# mainboard_rev_a.net
KiCad netlist of a schematic drawn in EAGLE
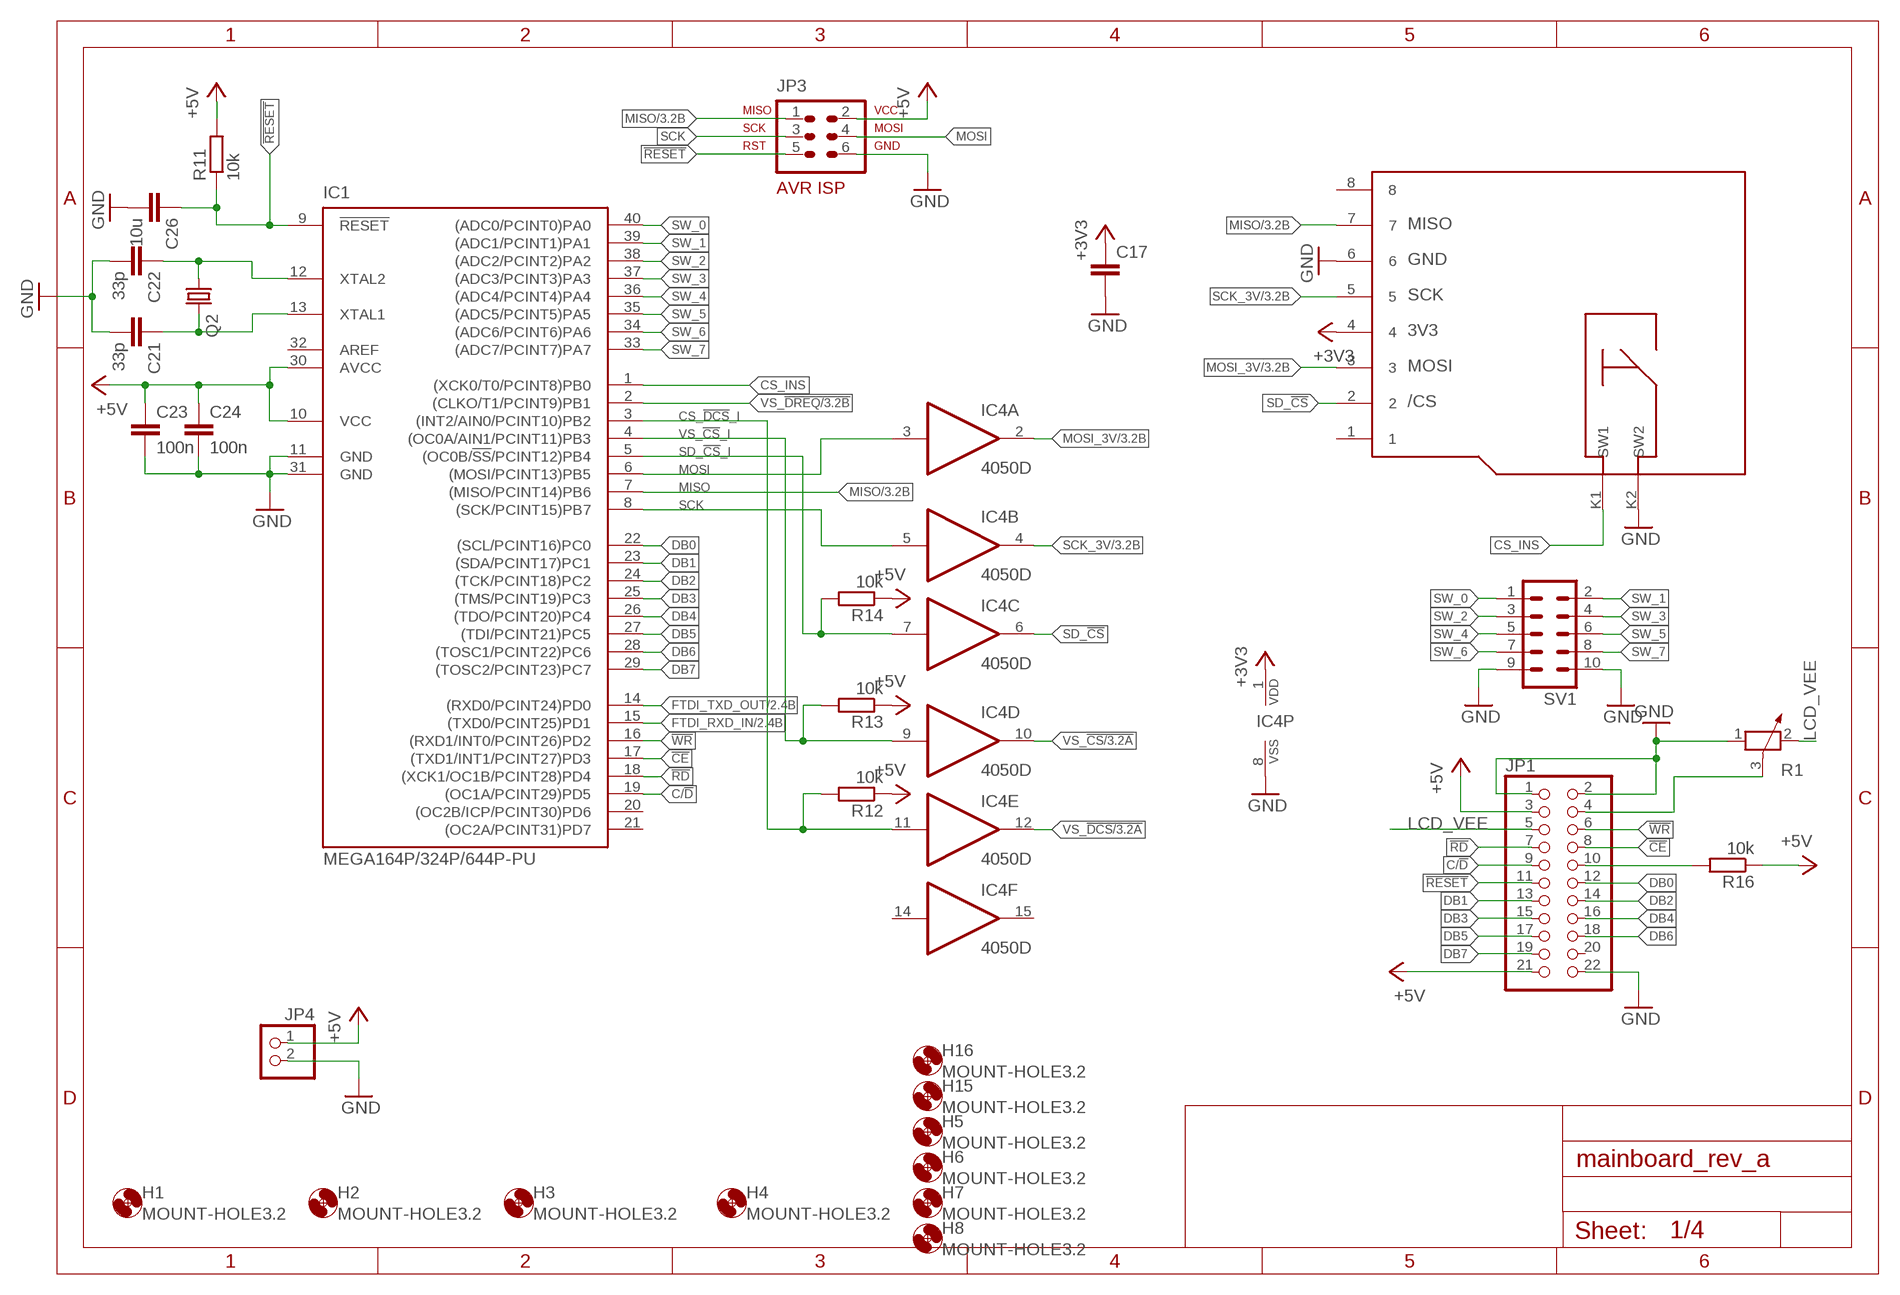
[diagram p0: schematic, sheet 1]
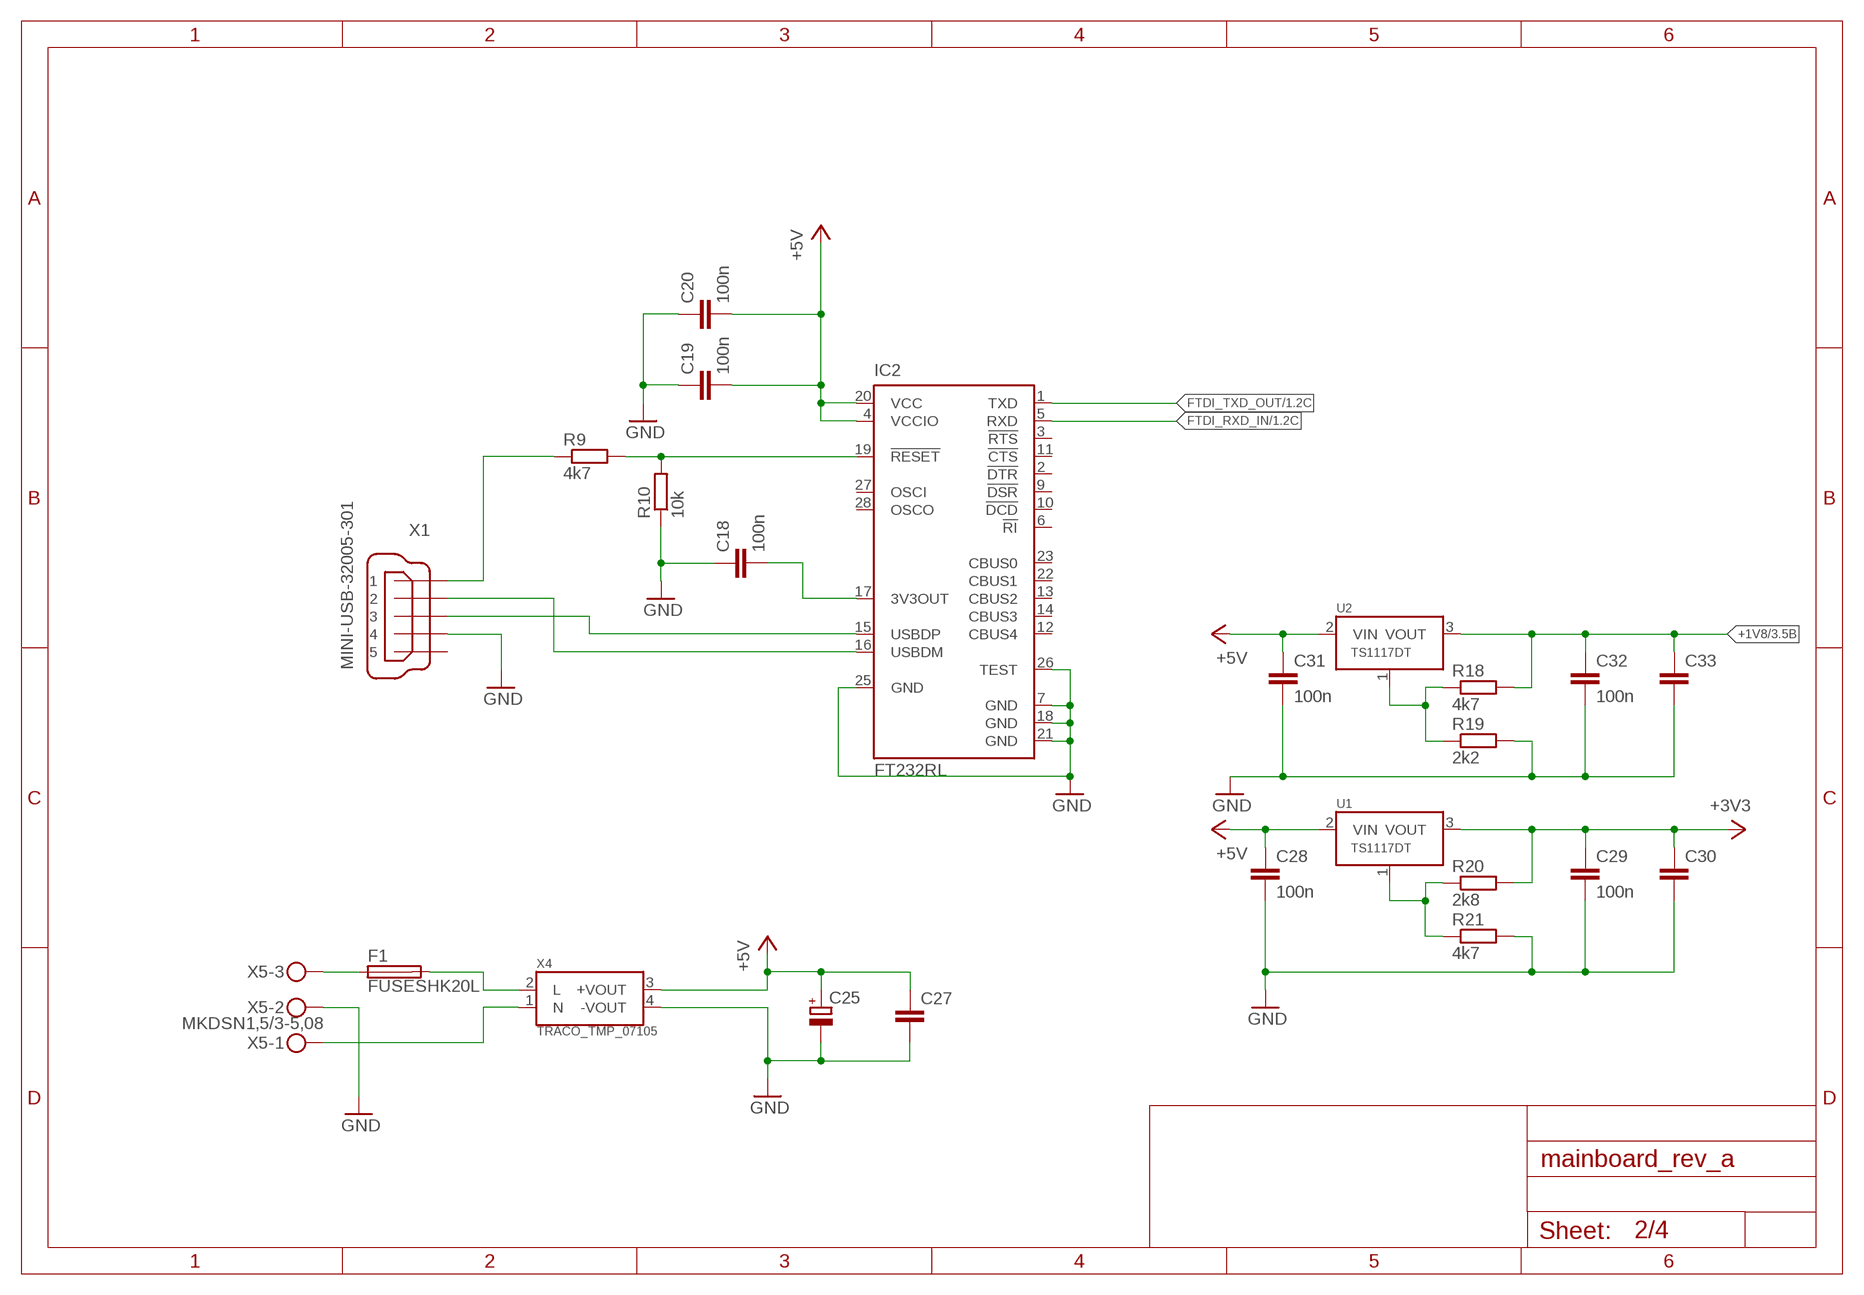
[diagram p1: schematic, sheet 2]
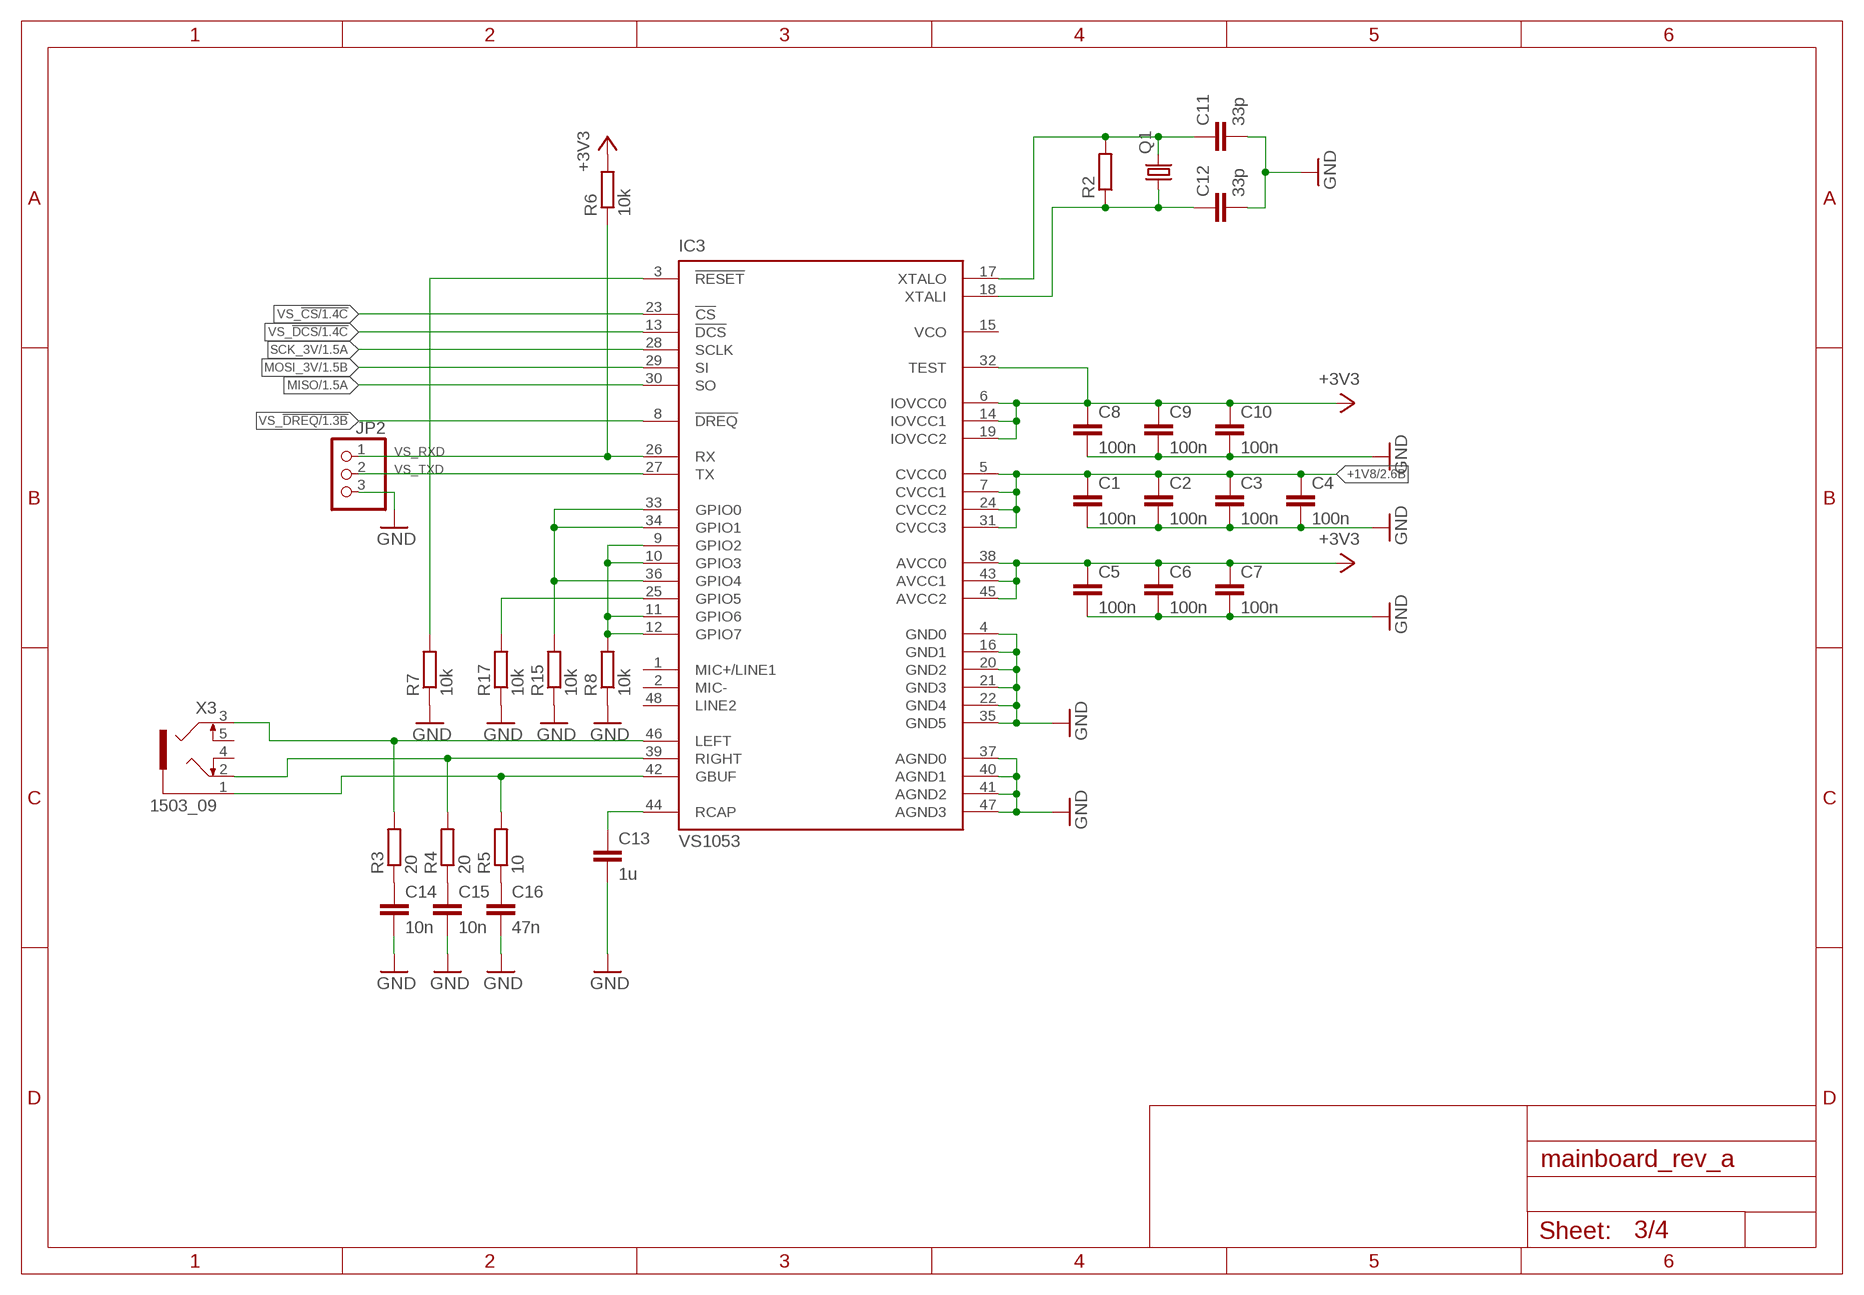
[diagram p2: schematic, sheet 3]
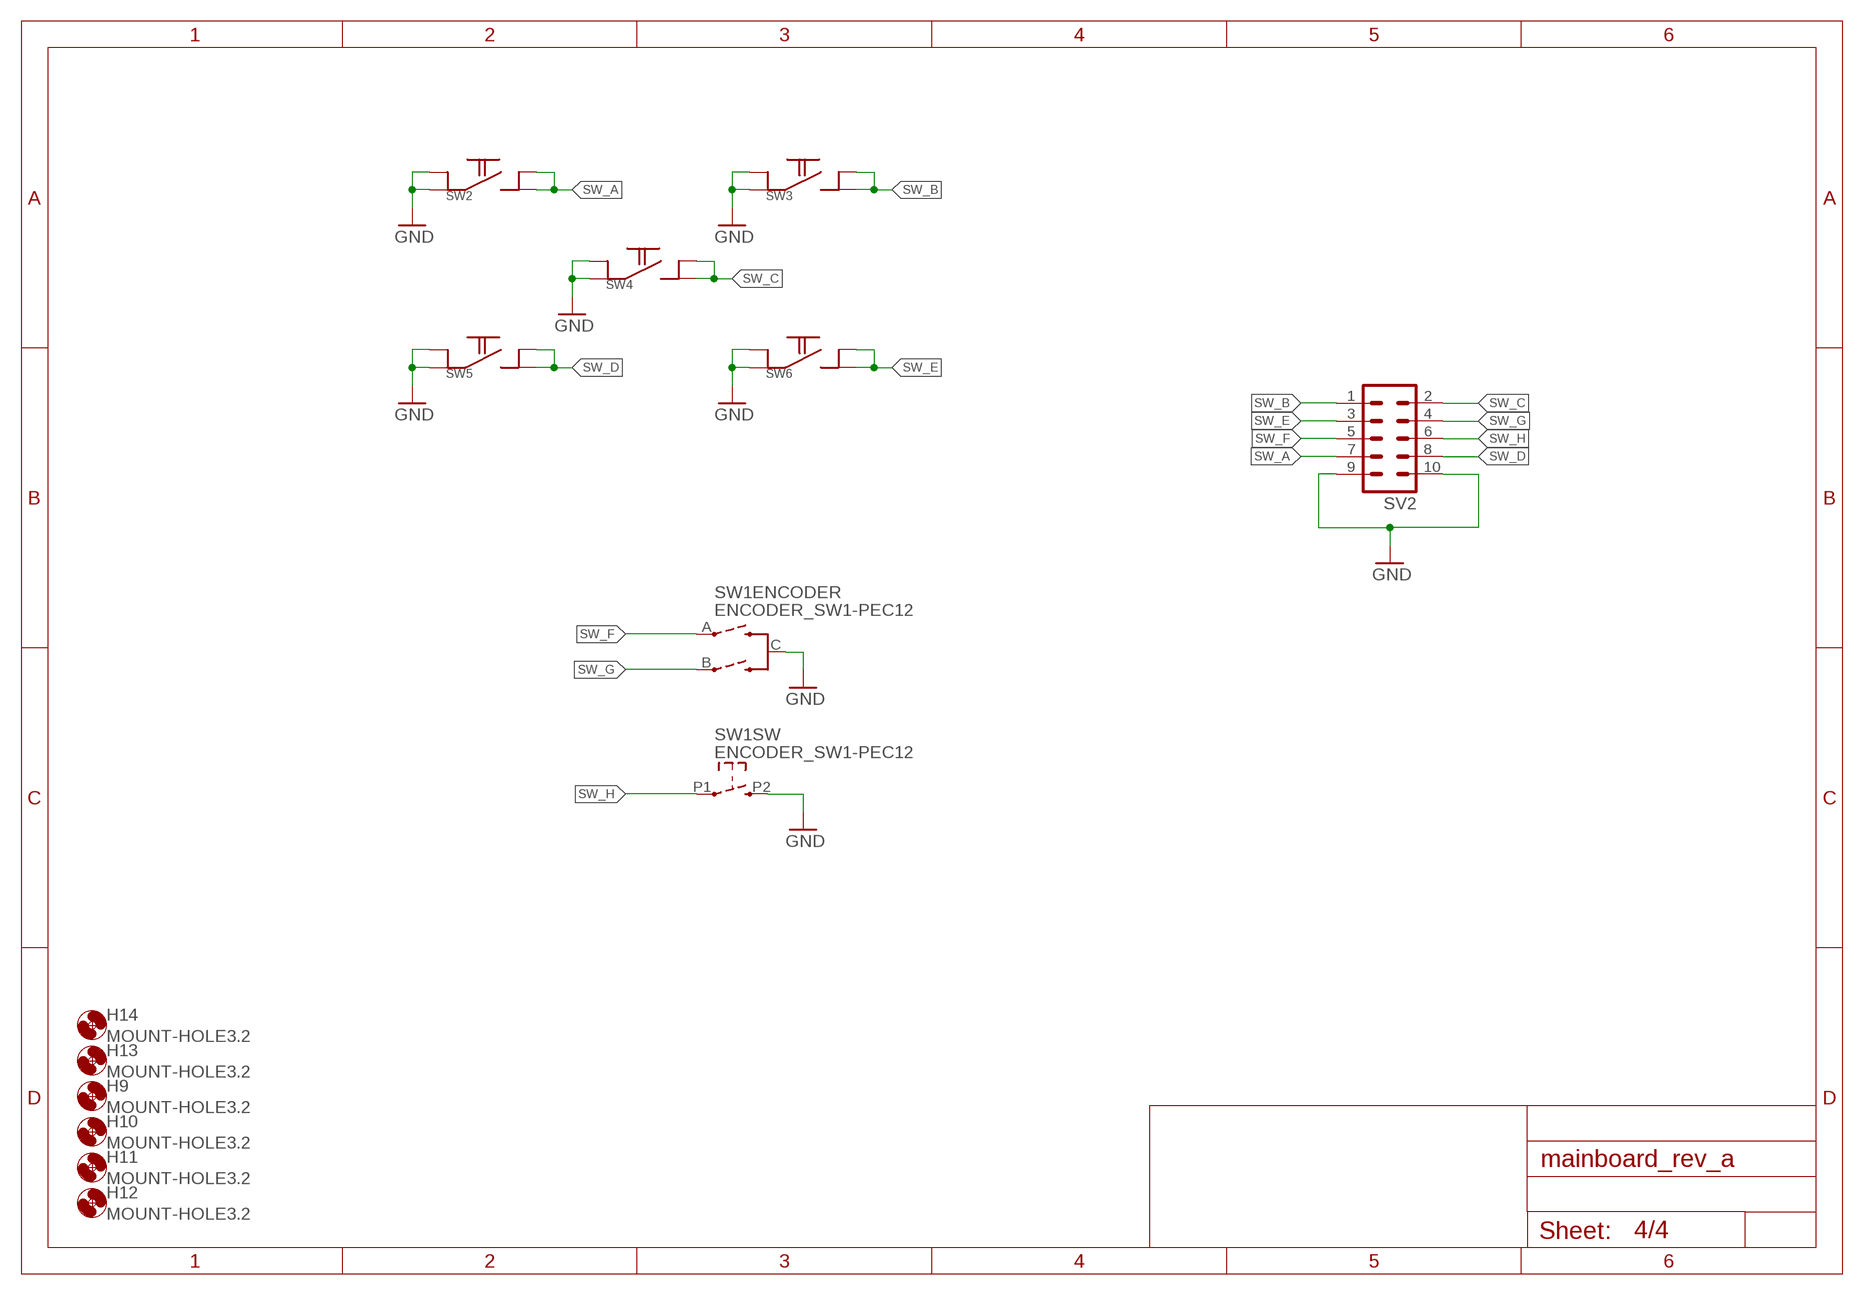
[diagram p3: schematic, sheet 4]

(export (version "E")
  (design (tool "Eeschema 10.0.6"))
  (components
    (comp (ref "H9")
      (value "MOUNT-HOLE3.2")
      (footprint "eagle-import:3,2")
      (libsource (lib "eagle-import") (part "MOUNT-HOLE3.2"))
    )
    (comp (ref "H10")
      (value "MOUNT-HOLE3.2")
      (footprint "eagle-import:3,2")
      (libsource (lib "eagle-import") (part "MOUNT-HOLE3.2"))
    )
    (comp (ref "H11")
      (value "MOUNT-HOLE3.2")
      (footprint "eagle-import:3,2")
      (libsource (lib "eagle-import") (part "MOUNT-HOLE3.2"))
    )
    (comp (ref "H12")
      (value "MOUNT-HOLE3.2")
      (footprint "eagle-import:3,2")
      (libsource (lib "eagle-import") (part "MOUNT-HOLE3.2"))
    )
    (comp (ref "H13")
      (value "MOUNT-HOLE3.2")
      (footprint "eagle-import:3,2")
      (libsource (lib "eagle-import") (part "MOUNT-HOLE3.2"))
    )
    (comp (ref "H14")
      (value "MOUNT-HOLE3.2")
      (footprint "eagle-import:3,2")
      (libsource (lib "eagle-import") (part "MOUNT-HOLE3.2"))
    )
    (comp (ref "SV2")
      (value "ML10")
      (footprint "eagle-import:ML10")
      (libsource (lib "eagle-import") (part "ML10"))
    )
    (comp (ref "SW1")
      (value "ENCODER_SW1-PEC12")
      (footprint "eagle-import:PEC12_INCREMENTAL_ENCODER")
      (libsource (lib "eagle-import") (part "ENCODER_SW1-PEC12"))
    )
    (comp (ref "SW2")
      (value "PUSHBUTTON_12X12")
      (footprint "eagle-import:PUSHBUTTON_12X12")
      (libsource (lib "eagle-import") (part "PUSHBUTTON_12X12"))
    )
    (comp (ref "SW3")
      (value "PUSHBUTTON_12X12")
      (footprint "eagle-import:PUSHBUTTON_12X12")
      (libsource (lib "eagle-import") (part "PUSHBUTTON_12X12"))
    )
    (comp (ref "SW4")
      (value "PUSHBUTTON_12X12")
      (footprint "eagle-import:PUSHBUTTON_12X12")
      (libsource (lib "eagle-import") (part "PUSHBUTTON_12X12"))
    )
    (comp (ref "SW5")
      (value "PUSHBUTTON_12X12")
      (footprint "eagle-import:PUSHBUTTON_12X12")
      (libsource (lib "eagle-import") (part "PUSHBUTTON_12X12"))
    )
    (comp (ref "SW6")
      (value "PUSHBUTTON_12X12")
      (footprint "eagle-import:PUSHBUTTON_12X12")
      (libsource (lib "eagle-import") (part "PUSHBUTTON_12X12"))
    )
    (comp (ref "C18")
      (value "100n")
      (footprint "eagle-import:C0603")
      (libsource (lib "eagle-import") (part "C-EUC0603"))
    )
    (comp (ref "C19")
      (value "100n")
      (footprint "eagle-import:C0603")
      (libsource (lib "eagle-import") (part "C-EUC0603"))
    )
    (comp (ref "C20")
      (value "100n")
      (footprint "eagle-import:C0603")
      (libsource (lib "eagle-import") (part "C-EUC0603"))
    )
    (comp (ref "C25")
      (value "CPOL-EU153CLV-0807")
      (footprint "eagle-import:153CLV-0807")
      (libsource (lib "eagle-import") (part "CPOL-EU153CLV-0807"))
    )
    (comp (ref "C27")
      (value "C-EUC1206")
      (footprint "eagle-import:C1206")
      (libsource (lib "eagle-import") (part "C-EUC1206"))
    )
    (comp (ref "C28")
      (value "100n")
      (footprint "eagle-import:C0603")
      (libsource (lib "eagle-import") (part "C-EUC0603"))
    )
    (comp (ref "C29")
      (value "100n")
      (footprint "eagle-import:C0603")
      (libsource (lib "eagle-import") (part "C-EUC0603"))
    )
    (comp (ref "C30")
      (value "C-EUC1206")
      (footprint "eagle-import:C1206")
      (libsource (lib "eagle-import") (part "C-EUC1206"))
    )
    (comp (ref "C31")
      (value "100n")
      (footprint "eagle-import:C0603")
      (libsource (lib "eagle-import") (part "C-EUC0603"))
    )
    (comp (ref "C32")
      (value "100n")
      (footprint "eagle-import:C0603")
      (libsource (lib "eagle-import") (part "C-EUC0603"))
    )
    (comp (ref "C33")
      (value "C-EUC1206")
      (footprint "eagle-import:C1206")
      (libsource (lib "eagle-import") (part "C-EUC1206"))
    )
    (comp (ref "F1")
      (value "FUSESHK20L")
      (footprint "eagle-import:SHK20L")
      (libsource (lib "eagle-import") (part "FUSESHK20L"))
    )
    (comp (ref "IC2")
      (value "FT232RL")
      (footprint "eagle-import:SSOP28")
      (libsource (lib "eagle-import") (part "FT232RL"))
    )
    (comp (ref "R9")
      (value "4k7")
      (footprint "eagle-import:R0603")
      (libsource (lib "eagle-import") (part "R-EU_R0603"))
    )
    (comp (ref "R10")
      (value "10k")
      (footprint "eagle-import:R0603")
      (libsource (lib "eagle-import") (part "R-EU_R0603"))
    )
    (comp (ref "R18")
      (value "4k7")
      (footprint "eagle-import:R0603")
      (libsource (lib "eagle-import") (part "R-EU_R0603"))
    )
    (comp (ref "R19")
      (value "2k2")
      (footprint "eagle-import:R0603")
      (libsource (lib "eagle-import") (part "R-EU_R0603"))
    )
    (comp (ref "R20")
      (value "2k8")
      (footprint "eagle-import:R0603")
      (libsource (lib "eagle-import") (part "R-EU_R0603"))
    )
    (comp (ref "R21")
      (value "4k7")
      (footprint "eagle-import:R0603")
      (libsource (lib "eagle-import") (part "R-EU_R0603"))
    )
    (comp (ref "U1")
      (value "TS1117DT")
      (footprint "eagle-import:TO252")
      (libsource (lib "eagle-import") (part "TS1117DT"))
    )
    (comp (ref "U2")
      (value "TS1117DT")
      (footprint "eagle-import:TO252")
      (libsource (lib "eagle-import") (part "TS1117DT"))
    )
    (comp (ref "X1")
      (value "MINI-USB-32005-301")
      (footprint "eagle-import:32005-301")
      (libsource (lib "eagle-import") (part "MINI-USB-32005-301"))
    )
    (comp (ref "X4")
      (value "TRACO_TMP_07105")
      (footprint "eagle-import:TRACO_TMP_07")
      (fields (field (name "MF") "TracoPower") (field (name "MPN") "TMP 07105"))
      (libsource (lib "eagle-import") (part "TRACO_TMP_07105"))
    )
    (comp (ref "X5")
      (value "MKDSN1,5/3-5,08")
      (footprint "eagle-import:MKDSN1,5_3-5,08")
      (fields (field (name "MPN") "SMKDSN1,5/3-5,08"))
      (libsource (lib "eagle-import") (part "MKDSN1,5/3-5,08"))
    )
    (comp (ref "C17")
      (value "C-EUC1206")
      (footprint "eagle-import:C1206")
      (libsource (lib "eagle-import") (part "C-EUC1206"))
    )
    (comp (ref "C21")
      (value "33p")
      (footprint "eagle-import:C0603")
      (libsource (lib "eagle-import") (part "C-EUC0603"))
    )
    (comp (ref "C22")
      (value "33p")
      (footprint "eagle-import:C0603")
      (libsource (lib "eagle-import") (part "C-EUC0603"))
    )
    (comp (ref "C23")
      (value "100n")
      (footprint "eagle-import:C0603")
      (libsource (lib "eagle-import") (part "C-EUC0603"))
    )
    (comp (ref "C24")
      (value "100n")
      (footprint "eagle-import:C0603")
      (libsource (lib "eagle-import") (part "C-EUC0603"))
    )
    (comp (ref "C26")
      (value "10u")
      (footprint "eagle-import:C1206")
      (libsource (lib "eagle-import") (part "C-EUC1206"))
    )
    (comp (ref "H1")
      (value "MOUNT-HOLE3.2")
      (footprint "eagle-import:3,2")
      (libsource (lib "eagle-import") (part "MOUNT-HOLE3.2"))
    )
    (comp (ref "H2")
      (value "MOUNT-HOLE3.2")
      (footprint "eagle-import:3,2")
      (libsource (lib "eagle-import") (part "MOUNT-HOLE3.2"))
    )
    (comp (ref "H3")
      (value "MOUNT-HOLE3.2")
      (footprint "eagle-import:3,2")
      (libsource (lib "eagle-import") (part "MOUNT-HOLE3.2"))
    )
    (comp (ref "H4")
      (value "MOUNT-HOLE3.2")
      (footprint "eagle-import:3,2")
      (libsource (lib "eagle-import") (part "MOUNT-HOLE3.2"))
    )
    (comp (ref "H5")
      (value "MOUNT-HOLE3.2")
      (footprint "eagle-import:3,2")
      (libsource (lib "eagle-import") (part "MOUNT-HOLE3.2"))
    )
    (comp (ref "H6")
      (value "MOUNT-HOLE3.2")
      (footprint "eagle-import:3,2")
      (libsource (lib "eagle-import") (part "MOUNT-HOLE3.2"))
    )
    (comp (ref "H7")
      (value "MOUNT-HOLE3.2")
      (footprint "eagle-import:3,2")
      (libsource (lib "eagle-import") (part "MOUNT-HOLE3.2"))
    )
    (comp (ref "H8")
      (value "MOUNT-HOLE3.2")
      (footprint "eagle-import:3,2")
      (libsource (lib "eagle-import") (part "MOUNT-HOLE3.2"))
    )
    (comp (ref "H15")
      (value "MOUNT-HOLE3.2")
      (footprint "eagle-import:3,2")
      (libsource (lib "eagle-import") (part "MOUNT-HOLE3.2"))
    )
    (comp (ref "H16")
      (value "MOUNT-HOLE3.2")
      (footprint "eagle-import:3,2")
      (libsource (lib "eagle-import") (part "MOUNT-HOLE3.2"))
    )
    (comp (ref "IC1")
      (value "MEGA164P/324P/644P-PU")
      (footprint "eagle-import:DIL40")
      (libsource (lib "eagle-import") (part "MEGA164P/324P/644P-PU"))
    )
    (comp (ref "IC4")
      (value "4050D")
      (footprint "eagle-import:SO16")
      (libsource (lib "eagle-import") (part "4050D"))
    )
    (comp (ref "JP1")
      (value "PINHD-2X11")
      (footprint "eagle-import:2X11")
      (libsource (lib "eagle-import") (part "PINHD-2X11"))
    )
    (comp (ref "JP3")
      (value "AVR-ISP-6VERT")
      (footprint "eagle-import:AVR-ISP-6")
      (libsource (lib "eagle-import") (part "AVR-ISP-6VERT"))
    )
    (comp (ref "JP4")
      (value "PINHD-1X2")
      (footprint "eagle-import:1X02")
      (libsource (lib "eagle-import") (part "PINHD-1X2"))
    )
    (comp (ref "Q2")
      (value "CRYSTALHC49UP")
      (footprint "eagle-import:HC49UP")
      (libsource (lib "eagle-import") (part "CRYSTALHC49UP"))
    )
    (comp (ref "R1")
      (value "POTENTIOMETER_PT_SPIN")
      (footprint "eagle-import:PT-SPIN")
      (libsource (lib "eagle-import") (part "POTENTIOMETER_PT_SPIN"))
    )
    (comp (ref "R11")
      (value "10k")
      (footprint "eagle-import:R0603")
      (libsource (lib "eagle-import") (part "R-EU_R0603"))
    )
    (comp (ref "R12")
      (value "10k")
      (footprint "eagle-import:R0603")
      (libsource (lib "eagle-import") (part "R-EU_R0603"))
    )
    (comp (ref "R13")
      (value "10k")
      (footprint "eagle-import:R0603")
      (libsource (lib "eagle-import") (part "R-EU_R0603"))
    )
    (comp (ref "R14")
      (value "10k")
      (footprint "eagle-import:R0603")
      (libsource (lib "eagle-import") (part "R-EU_R0603"))
    )
    (comp (ref "R16")
      (value "10k")
      (footprint "eagle-import:R0603")
      (libsource (lib "eagle-import") (part "R-EU_R0603"))
    )
    (comp (ref "SV1")
      (value "ML10")
      (footprint "eagle-import:ML10")
      (libsource (lib "eagle-import") (part "ML10"))
    )
    (comp (ref "X2")
      (value "MICRO-SD")
      (footprint "eagle-import:MICRO-SD")
      (libsource (lib "eagle-import") (part "MICRO-SD"))
    )
    (comp (ref "C1")
      (value "100n")
      (footprint "eagle-import:C0603")
      (libsource (lib "eagle-import") (part "C-EUC0603"))
    )
    (comp (ref "C2")
      (value "100n")
      (footprint "eagle-import:C0603")
      (libsource (lib "eagle-import") (part "C-EUC0603"))
    )
    (comp (ref "C3")
      (value "100n")
      (footprint "eagle-import:C0603")
      (libsource (lib "eagle-import") (part "C-EUC0603"))
    )
    (comp (ref "C4")
      (value "100n")
      (footprint "eagle-import:C0603")
      (libsource (lib "eagle-import") (part "C-EUC0603"))
    )
    (comp (ref "C5")
      (value "100n")
      (footprint "eagle-import:C0603")
      (libsource (lib "eagle-import") (part "C-EUC0603"))
    )
    (comp (ref "C6")
      (value "100n")
      (footprint "eagle-import:C0603")
      (libsource (lib "eagle-import") (part "C-EUC0603"))
    )
    (comp (ref "C7")
      (value "100n")
      (footprint "eagle-import:C0603")
      (libsource (lib "eagle-import") (part "C-EUC0603"))
    )
    (comp (ref "C8")
      (value "100n")
      (footprint "eagle-import:C0603")
      (libsource (lib "eagle-import") (part "C-EUC0603"))
    )
    (comp (ref "C9")
      (value "100n")
      (footprint "eagle-import:C0603")
      (libsource (lib "eagle-import") (part "C-EUC0603"))
    )
    (comp (ref "C10")
      (value "100n")
      (footprint "eagle-import:C0603")
      (libsource (lib "eagle-import") (part "C-EUC0603"))
    )
    (comp (ref "C11")
      (value "33p")
      (footprint "eagle-import:C0603")
      (libsource (lib "eagle-import") (part "C-EUC0603"))
    )
    (comp (ref "C12")
      (value "33p")
      (footprint "eagle-import:C0603")
      (libsource (lib "eagle-import") (part "C-EUC0603"))
    )
    (comp (ref "C13")
      (value "1u")
      (footprint "eagle-import:C0805")
      (libsource (lib "eagle-import") (part "C-EUC0805"))
    )
    (comp (ref "C14")
      (value "10n")
      (footprint "eagle-import:C0603")
      (libsource (lib "eagle-import") (part "C-EUC0603"))
    )
    (comp (ref "C15")
      (value "10n")
      (footprint "eagle-import:C0603")
      (libsource (lib "eagle-import") (part "C-EUC0603"))
    )
    (comp (ref "C16")
      (value "47n")
      (footprint "eagle-import:C0603")
      (libsource (lib "eagle-import") (part "C-EUC0603"))
    )
    (comp (ref "IC3")
      (value "VS1053")
      (footprint "eagle-import:LQFP-48")
      (libsource (lib "eagle-import") (part "VS1053"))
    )
    (comp (ref "JP2")
      (value "PINHD-1X3")
      (footprint "eagle-import:1X03")
      (libsource (lib "eagle-import") (part "PINHD-1X3"))
    )
    (comp (ref "Q1")
      (value "CRYSTALHC49UP")
      (footprint "eagle-import:HC49UP")
      (libsource (lib "eagle-import") (part "CRYSTALHC49UP"))
    )
    (comp (ref "R2")
      (value "R-EU_R0603")
      (footprint "eagle-import:R0603")
      (libsource (lib "eagle-import") (part "R-EU_R0603"))
    )
    (comp (ref "R3")
      (value "20")
      (footprint "eagle-import:R0603")
      (libsource (lib "eagle-import") (part "R-EU_R0603"))
    )
    (comp (ref "R4")
      (value "20")
      (footprint "eagle-import:R0603")
      (libsource (lib "eagle-import") (part "R-EU_R0603"))
    )
    (comp (ref "R5")
      (value "10")
      (footprint "eagle-import:R0603")
      (libsource (lib "eagle-import") (part "R-EU_R0603"))
    )
    (comp (ref "R6")
      (value "10k")
      (footprint "eagle-import:R0603")
      (libsource (lib "eagle-import") (part "R-EU_R0603"))
    )
    (comp (ref "R7")
      (value "10k")
      (footprint "eagle-import:R0603")
      (libsource (lib "eagle-import") (part "R-EU_R0603"))
    )
    (comp (ref "R8")
      (value "10k")
      (footprint "eagle-import:R0603")
      (libsource (lib "eagle-import") (part "R-EU_R0603"))
    )
    (comp (ref "R15")
      (value "10k")
      (footprint "eagle-import:R0603")
      (libsource (lib "eagle-import") (part "R-EU_R0603"))
    )
    (comp (ref "R17")
      (value "10k")
      (footprint "eagle-import:R0603")
      (libsource (lib "eagle-import") (part "R-EU_R0603"))
    )
    (comp (ref "X3")
      (value "1503_09")
      (footprint "eagle-import:1503_09")
      (libsource (lib "eagle-import") (part "1503_09"))
    )
  )
  (nets
    (net (code "1") (name "+1V8") (class "Default")
      (node (ref "C1") (pin "1") (pinfunction "1_1") (pintype "passive"))
      (node (ref "C2") (pin "1") (pinfunction "1_1") (pintype "passive"))
      (node (ref "C3") (pin "1") (pinfunction "1_1") (pintype "passive"))
      (node (ref "C32") (pin "1") (pinfunction "1_1") (pintype "passive"))
      (node (ref "C33") (pin "1") (pinfunction "1_1") (pintype "passive"))
      (node (ref "C4") (pin "1") (pinfunction "1_1") (pintype "passive"))
      (node (ref "IC3") (pin "24") (pinfunction "CVCC2_24") (pintype "power_in"))
      (node (ref "IC3") (pin "31") (pinfunction "CVCC3_31") (pintype "power_in"))
      (node (ref "IC3") (pin "5") (pinfunction "CVCC0_5") (pintype "power_in"))
      (node (ref "IC3") (pin "7") (pinfunction "CVCC1_7") (pintype "power_in"))
      (node (ref "R18") (pin "2") (pinfunction "2_2") (pintype "passive"))
      (node (ref "U2") (pin "3") (pinfunction "VOUT_3") (pintype "power_in"))
    )
    (net (code "2") (name "+3V3") (class "Default")
      (node (ref "C10") (pin "1") (pinfunction "1_1") (pintype "passive"))
      (node (ref "C17") (pin "1") (pinfunction "1_1") (pintype "passive"))
      (node (ref "C29") (pin "1") (pinfunction "1_1") (pintype "passive"))
      (node (ref "C30") (pin "1") (pinfunction "1_1") (pintype "passive"))
      (node (ref "C5") (pin "1") (pinfunction "1_1") (pintype "passive"))
      (node (ref "C6") (pin "1") (pinfunction "1_1") (pintype "passive"))
      (node (ref "C7") (pin "1") (pinfunction "1_1") (pintype "passive"))
      (node (ref "C8") (pin "1") (pinfunction "1_1") (pintype "passive"))
      (node (ref "C9") (pin "1") (pinfunction "1_1") (pintype "passive"))
      (node (ref "IC3") (pin "14") (pinfunction "IOVCC1_14") (pintype "power_in"))
      (node (ref "IC3") (pin "19") (pinfunction "IOVCC2_19") (pintype "power_in"))
      (node (ref "IC3") (pin "32") (pinfunction "TEST_32") (pintype "input"))
      (node (ref "IC3") (pin "38") (pinfunction "AVCC0_38") (pintype "power_in"))
      (node (ref "IC3") (pin "43") (pinfunction "AVCC1_43") (pintype "power_in"))
      (node (ref "IC3") (pin "45") (pinfunction "AVCC2_45") (pintype "power_in"))
      (node (ref "IC3") (pin "6") (pinfunction "IOVCC0_6") (pintype "power_in"))
      (node (ref "IC4") (pin "1") (pinfunction "VDD_1") (pintype "power_in"))
      (node (ref "R20") (pin "2") (pinfunction "2_2") (pintype "passive"))
      (node (ref "R6") (pin "2") (pinfunction "2_2") (pintype "passive"))
      (node (ref "U1") (pin "3") (pinfunction "VOUT_3") (pintype "power_in"))
      (node (ref "X2") (pin "4") (pinfunction "4_4") (pintype "bidirectional"))
    )
    (net (code "3") (name "+5V") (class "Default")
      (node (ref "C19") (pin "2") (pinfunction "2_2") (pintype "passive"))
      (node (ref "C20") (pin "2") (pinfunction "2_2") (pintype "passive"))
      (node (ref "C23") (pin "1") (pinfunction "1_1") (pintype "passive"))
      (node (ref "C24") (pin "1") (pinfunction "1_1") (pintype "passive"))
      (node (ref "C25") (pin "+") (pinfunction "+_+") (pintype "passive"))
      (node (ref "C27") (pin "1") (pinfunction "1_1") (pintype "passive"))
      (node (ref "C28") (pin "1") (pinfunction "1_1") (pintype "passive"))
      (node (ref "C31") (pin "1") (pinfunction "1_1") (pintype "passive"))
      (node (ref "IC1") (pin "10") (pinfunction "VCC_10") (pintype "power_in"))
      (node (ref "IC1") (pin "30") (pinfunction "AVCC_30") (pintype "power_in"))
      (node (ref "IC2") (pin "20") (pinfunction "VCC_20") (pintype "power_in"))
      (node (ref "IC2") (pin "4") (pinfunction "VCCIO_4") (pintype "power_in"))
      (node (ref "JP1") (pin "21") (pinfunction "21_21") (pintype "passive"))
      (node (ref "JP1") (pin "3") (pinfunction "3_3") (pintype "passive"))
      (node (ref "JP3") (pin "2") (pinfunction "2_2") (pintype "passive"))
      (node (ref "JP4") (pin "1") (pinfunction "1_1") (pintype "passive"))
      (node (ref "R11") (pin "2") (pinfunction "2_2") (pintype "passive"))
      (node (ref "R12") (pin "1") (pinfunction "1_1") (pintype "passive"))
      (node (ref "R13") (pin "1") (pinfunction "1_1") (pintype "passive"))
      (node (ref "R14") (pin "1") (pinfunction "1_1") (pintype "passive"))
      (node (ref "R16") (pin "1") (pinfunction "1_1") (pintype "passive"))
      (node (ref "U1") (pin "2") (pinfunction "VIN_2") (pintype "power_in"))
      (node (ref "U2") (pin "2") (pinfunction "VIN_2") (pintype "power_in"))
      (node (ref "X4") (pin "3") (pinfunction "+VOUT_3") (pintype "output"))
    )
    (net (code "4") (name "AREF") (class "Default")
      (node (ref "IC1") (pin "32") (pinfunction "AREF_32") (pintype "power_in"))
    )
    (net (code "5") (name "CS_INS") (class "Default")
      (node (ref "IC1") (pin "1") (pinfunction "(XCK0/T0/PCINT8)PB0_1") (pintype "bidirectional"))
      (node (ref "X2") (pin "K1") (pinfunction "SW1_K1") (pintype "bidirectional"))
    )
    (net (code "6") (name "CS_~{DCS}_I") (class "Default")
      (node (ref "IC1") (pin "3") (pinfunction "(INT2/AIN0/PCINT10)PB2_3") (pintype "bidirectional"))
      (node (ref "IC4") (pin "11") (pinfunction "I_11") (pintype "input"))
      (node (ref "R12") (pin "2") (pinfunction "2_2") (pintype "passive"))
    )
    (net (code "7") (name "C{slash}~{D}") (class "Default")
      (node (ref "IC1") (pin "19") (pinfunction "(OC1A/PCINT29)PD5_19") (pintype "bidirectional"))
      (node (ref "JP1") (pin "9") (pinfunction "9_9") (pintype "passive"))
    )
    (net (code "8") (name "DB0") (class "Default")
      (node (ref "IC1") (pin "22") (pinfunction "(SCL/PCINT16)PC0_22") (pintype "bidirectional"))
      (node (ref "JP1") (pin "12") (pinfunction "12_12") (pintype "passive"))
    )
    (net (code "9") (name "DB1") (class "Default")
      (node (ref "IC1") (pin "23") (pinfunction "(SDA/PCINT17)PC1_23") (pintype "bidirectional"))
      (node (ref "JP1") (pin "13") (pinfunction "13_13") (pintype "passive"))
    )
    (net (code "10") (name "DB2") (class "Default")
      (node (ref "IC1") (pin "24") (pinfunction "(TCK/PCINT18)PC2_24") (pintype "bidirectional"))
      (node (ref "JP1") (pin "14") (pinfunction "14_14") (pintype "passive"))
    )
    (net (code "11") (name "DB3") (class "Default")
      (node (ref "IC1") (pin "25") (pinfunction "(TMS/PCINT19)PC3_25") (pintype "bidirectional"))
      (node (ref "JP1") (pin "15") (pinfunction "15_15") (pintype "passive"))
    )
    (net (code "12") (name "DB4") (class "Default")
      (node (ref "IC1") (pin "26") (pinfunction "(TDO/PCINT20)PC4_26") (pintype "bidirectional"))
      (node (ref "JP1") (pin "16") (pinfunction "16_16") (pintype "passive"))
    )
    (net (code "13") (name "DB5") (class "Default")
      (node (ref "IC1") (pin "27") (pinfunction "(TDI/PCINT21)PC5_27") (pintype "bidirectional"))
      (node (ref "JP1") (pin "17") (pinfunction "17_17") (pintype "passive"))
    )
    (net (code "14") (name "DB6") (class "Default")
      (node (ref "IC1") (pin "28") (pinfunction "(TOSC1/PCINT22)PC6_28") (pintype "bidirectional"))
      (node (ref "JP1") (pin "18") (pinfunction "18_18") (pintype "passive"))
    )
    (net (code "15") (name "DB7") (class "Default")
      (node (ref "IC1") (pin "29") (pinfunction "(TOSC2/PCINT23)PC7_29") (pintype "bidirectional"))
      (node (ref "JP1") (pin "19") (pinfunction "19_19") (pintype "passive"))
    )
    (net (code "16") (name "FTDI_RXD_IN") (class "Default")
      (node (ref "IC1") (pin "15") (pinfunction "(TXD0/PCINT25)PD1_15") (pintype "bidirectional"))
      (node (ref "IC2") (pin "5") (pinfunction "RXD_5") (pintype "input"))
    )
    (net (code "17") (name "FTDI_TXD_OUT") (class "Default")
      (node (ref "IC1") (pin "14") (pinfunction "(RXD0/PCINT24)PD0_14") (pintype "bidirectional"))
      (node (ref "IC2") (pin "1") (pinfunction "TXD_1") (pintype "output"))
    )
    (net (code "18") (name "GND") (class "Default")
      (node (ref "C1") (pin "2") (pinfunction "2_2") (pintype "passive"))
      (node (ref "C10") (pin "2") (pinfunction "2_2") (pintype "passive"))
      (node (ref "C11") (pin "2") (pinfunction "2_2") (pintype "passive"))
      (node (ref "C12") (pin "2") (pinfunction "2_2") (pintype "passive"))
      (node (ref "C13") (pin "2") (pinfunction "2_2") (pintype "passive"))
      (node (ref "C14") (pin "2") (pinfunction "2_2") (pintype "passive"))
      (node (ref "C15") (pin "2") (pinfunction "2_2") (pintype "passive"))
      (node (ref "C16") (pin "2") (pinfunction "2_2") (pintype "passive"))
      (node (ref "C17") (pin "2") (pinfunction "2_2") (pintype "passive"))
      (node (ref "C18") (pin "1") (pinfunction "1_1") (pintype "passive"))
      (node (ref "C19") (pin "1") (pinfunction "1_1") (pintype "passive"))
      (node (ref "C2") (pin "2") (pinfunction "2_2") (pintype "passive"))
      (node (ref "C20") (pin "1") (pinfunction "1_1") (pintype "passive"))
      (node (ref "C21") (pin "2") (pinfunction "2_2") (pintype "passive"))
      (node (ref "C22") (pin "2") (pinfunction "2_2") (pintype "passive"))
      (node (ref "C23") (pin "2") (pinfunction "2_2") (pintype "passive"))
      (node (ref "C24") (pin "2") (pinfunction "2_2") (pintype "passive"))
      (node (ref "C25") (pin "-") (pinfunction "-_-") (pintype "passive"))
      (node (ref "C26") (pin "2") (pinfunction "2_2") (pintype "passive"))
      (node (ref "C27") (pin "2") (pinfunction "2_2") (pintype "passive"))
      (node (ref "C28") (pin "2") (pinfunction "2_2") (pintype "passive"))
      (node (ref "C29") (pin "2") (pinfunction "2_2") (pintype "passive"))
      (node (ref "C3") (pin "2") (pinfunction "2_2") (pintype "passive"))
      (node (ref "C30") (pin "2") (pinfunction "2_2") (pintype "passive"))
      (node (ref "C31") (pin "2") (pinfunction "2_2") (pintype "passive"))
      (node (ref "C32") (pin "2") (pinfunction "2_2") (pintype "passive"))
      (node (ref "C33") (pin "2") (pinfunction "2_2") (pintype "passive"))
      (node (ref "C4") (pin "2") (pinfunction "2_2") (pintype "passive"))
      (node (ref "C5") (pin "2") (pinfunction "2_2") (pintype "passive"))
      (node (ref "C6") (pin "2") (pinfunction "2_2") (pintype "passive"))
      (node (ref "C7") (pin "2") (pinfunction "2_2") (pintype "passive"))
      (node (ref "C8") (pin "2") (pinfunction "2_2") (pintype "passive"))
      (node (ref "C9") (pin "2") (pinfunction "2_2") (pintype "passive"))
      (node (ref "IC1") (pin "11") (pinfunction "GND_11") (pintype "power_in"))
      (node (ref "IC1") (pin "31") (pinfunction "GND_31") (pintype "power_in"))
      (node (ref "IC2") (pin "18") (pinfunction "GND_18") (pintype "power_in"))
      (node (ref "IC2") (pin "21") (pinfunction "GND_21") (pintype "power_in"))
      (node (ref "IC2") (pin "25") (pinfunction "GND_25") (pintype "power_in"))
      (node (ref "IC2") (pin "26") (pinfunction "TEST_26") (pintype "input"))
      (node (ref "IC2") (pin "7") (pinfunction "GND_7") (pintype "power_in"))
      (node (ref "IC3") (pin "16") (pinfunction "GND1_16") (pintype "power_in"))
      (node (ref "IC3") (pin "20") (pinfunction "GND2_20") (pintype "power_in"))
      (node (ref "IC3") (pin "21") (pinfunction "GND3_21") (pintype "power_in"))
      (node (ref "IC3") (pin "22") (pinfunction "GND4_22") (pintype "power_in"))
      (node (ref "IC3") (pin "35") (pinfunction "GND5_35") (pintype "power_in"))
      (node (ref "IC3") (pin "37") (pinfunction "AGND0_37") (pintype "power_in"))
      (node (ref "IC3") (pin "4") (pinfunction "GND0_4") (pintype "power_in"))
      (node (ref "IC3") (pin "40") (pinfunction "AGND1_40") (pintype "power_in"))
      (node (ref "IC3") (pin "41") (pinfunction "AGND2_41") (pintype "power_in"))
      (node (ref "IC3") (pin "47") (pinfunction "AGND3_47") (pintype "power_in"))
      (node (ref "IC4") (pin "8") (pinfunction "VSS_8") (pintype "power_in"))
      (node (ref "JP1") (pin "1") (pinfunction "1_1") (pintype "passive"))
      (node (ref "JP1") (pin "2") (pinfunction "2_2") (pintype "passive"))
      (node (ref "JP1") (pin "22") (pinfunction "22_22") (pintype "passive"))
      (node (ref "JP2") (pin "3") (pinfunction "3_3") (pintype "passive"))
      (node (ref "JP3") (pin "6") (pinfunction "6_6") (pintype "passive"))
      (node (ref "JP4") (pin "2") (pinfunction "2_2") (pintype "passive"))
      (node (ref "R1") (pin "1") (pinfunction "1_1") (pintype "passive"))
      (node (ref "R10") (pin "1") (pinfunction "1_1") (pintype "passive"))
      (node (ref "R15") (pin "1") (pinfunction "1_1") (pintype "passive"))
      (node (ref "R17") (pin "1") (pinfunction "1_1") (pintype "passive"))
      (node (ref "R19") (pin "2") (pinfunction "2_2") (pintype "passive"))
      (node (ref "R21") (pin "2") (pinfunction "2_2") (pintype "passive"))
      (node (ref "R7") (pin "1") (pinfunction "1_1") (pintype "passive"))
      (node (ref "R8") (pin "1") (pinfunction "1_1") (pintype "passive"))
      (node (ref "SV1") (pin "10") (pinfunction "10_10") (pintype "passive"))
      (node (ref "SV1") (pin "9") (pinfunction "9_9") (pintype "passive"))
      (node (ref "SV2") (pin "10") (pinfunction "10_10") (pintype "passive"))
      (node (ref "SV2") (pin "9") (pinfunction "9_9") (pintype "passive"))
      (node (ref "SW1") (pin "C") (pinfunction "C_C") (pintype "passive"))
      (node (ref "SW1") (pin "P2") (pinfunction "2_P2") (pintype "passive"))
      (node (ref "SW2") (pin "A@1") (pinfunction "A_A@1") (pintype "passive"))
      (node (ref "SW2") (pin "A@2") (pinfunction "A_A@2") (pintype "passive"))
      (node (ref "SW3") (pin "A@1") (pinfunction "A_A@1") (pintype "passive"))
      (node (ref "SW3") (pin "A@2") (pinfunction "A_A@2") (pintype "passive"))
      (node (ref "SW4") (pin "A@1") (pinfunction "A_A@1") (pintype "passive"))
      (node (ref "SW4") (pin "A@2") (pinfunction "A_A@2") (pintype "passive"))
      (node (ref "SW5") (pin "A@1") (pinfunction "A_A@1") (pintype "passive"))
      (node (ref "SW5") (pin "A@2") (pinfunction "A_A@2") (pintype "passive"))
      (node (ref "SW6") (pin "A@1") (pinfunction "A_A@1") (pintype "passive"))
      (node (ref "SW6") (pin "A@2") (pinfunction "A_A@2") (pintype "passive"))
      (node (ref "X1") (pin "4") (pinfunction "4_4") (pintype "passive"))
      (node (ref "X2") (pin "6") (pinfunction "6_6") (pintype "bidirectional"))
      (node (ref "X2") (pin "K2") (pinfunction "SW2_K2") (pintype "bidirectional"))
      (node (ref "X4") (pin "4") (pinfunction "-VOUT_4") (pintype "output"))
      (node (ref "X5") (pin "2") (pinfunction "KL_2") (pintype "passive"))
    )
    (net (code "19") (name "LCD_VEE") (class "Default")
      (node (ref "JP1") (pin "5") (pinfunction "5_5") (pintype "passive"))
      (node (ref "R1") (pin "2") (pinfunction "2_2") (pintype "passive"))
    )
    (net (code "20") (name "MISO") (class "Default")
      (node (ref "IC1") (pin "7") (pinfunction "(MISO/PCINT14)PB6_7") (pintype "bidirectional"))
      (node (ref "IC3") (pin "30") (pinfunction "SO_30") (pintype "output"))
      (node (ref "JP3") (pin "1") (pinfunction "1_1") (pintype "passive"))
      (node (ref "X2") (pin "7") (pinfunction "7_7") (pintype "bidirectional"))
    )
    (net (code "21") (name "MOSI") (class "Default")
      (node (ref "IC1") (pin "6") (pinfunction "(MOSI/PCINT13)PB5_6") (pintype "bidirectional"))
      (node (ref "IC4") (pin "3") (pinfunction "I_3") (pintype "input"))
      (node (ref "JP3") (pin "4") (pinfunction "4_4") (pintype "passive"))
    )
    (net (code "22") (name "MOSI_3V") (class "Default")
      (node (ref "IC3") (pin "29") (pinfunction "SI_29") (pintype "input"))
      (node (ref "IC4") (pin "2") (pinfunction "O_2") (pintype "output"))
      (node (ref "X2") (pin "3") (pinfunction "3_3") (pintype "bidirectional"))
    )
    (net (code "23") (name "Net-(C14-Pad1)") (class "Default")
      (node (ref "C14") (pin "1") (pinfunction "1_1") (pintype "passive"))
      (node (ref "R3") (pin "1") (pinfunction "1_1") (pintype "passive"))
    )
    (net (code "24") (name "Net-(C15-Pad1)") (class "Default")
      (node (ref "C15") (pin "1") (pinfunction "1_1") (pintype "passive"))
      (node (ref "R4") (pin "1") (pinfunction "1_1") (pintype "passive"))
    )
    (net (code "25") (name "Net-(C16-Pad1)") (class "Default")
      (node (ref "C16") (pin "1") (pinfunction "1_1") (pintype "passive"))
      (node (ref "R5") (pin "1") (pinfunction "1_1") (pintype "passive"))
    )
    (net (code "26") (name "Net-(F1-1)") (class "Default")
      (node (ref "F1") (pin "1A") (pinfunction "1_1A") (pintype "passive"))
      (node (ref "X5") (pin "3") (pinfunction "KL_3") (pintype "passive"))
    )
    (net (code "27") (name "Net-(F1-2)") (class "Default")
      (node (ref "F1") (pin "2A") (pinfunction "2_2A") (pintype "passive"))
      (node (ref "X4") (pin "2") (pinfunction "L_2") (pintype "input"))
    )
    (net (code "28") (name "Net-(IC1-XTAL1)") (class "Default")
      (node (ref "C21") (pin "1") (pinfunction "1_1") (pintype "passive"))
      (node (ref "IC1") (pin "13") (pinfunction "XTAL1_13") (pintype "input"))
      (node (ref "Q2") (pin "2") (pinfunction "2_2") (pintype "passive"))
    )
    (net (code "29") (name "Net-(IC1-XTAL2)") (class "Default")
      (node (ref "C22") (pin "1") (pinfunction "1_1") (pintype "passive"))
      (node (ref "IC1") (pin "12") (pinfunction "XTAL2_12") (pintype "output"))
      (node (ref "Q2") (pin "1") (pinfunction "1_1") (pintype "passive"))
    )
    (net (code "30") (name "Net-(IC2-3V3OUT)") (class "Default")
      (node (ref "C18") (pin "2") (pinfunction "2_2") (pintype "passive"))
      (node (ref "IC2") (pin "17") (pinfunction "3V3OUT_17") (pintype "output"))
    )
    (net (code "31") (name "Net-(IC2-USBDM)") (class "Default")
      (node (ref "IC2") (pin "16") (pinfunction "USBDM_16") (pintype "bidirectional"))
      (node (ref "X1") (pin "2") (pinfunction "2_2") (pintype "passive"))
    )
    (net (code "32") (name "Net-(IC2-USBDP)") (class "Default")
      (node (ref "IC2") (pin "15") (pinfunction "USBDP_15") (pintype "bidirectional"))
      (node (ref "X1") (pin "3") (pinfunction "3_3") (pintype "passive"))
    )
    (net (code "33") (name "Net-(IC2-~{RESET})") (class "Default")
      (node (ref "IC2") (pin "19") (pinfunction "~{RESET}_19") (pintype "input"))
      (node (ref "R10") (pin "2") (pinfunction "2_2") (pintype "passive"))
      (node (ref "R9") (pin "2") (pinfunction "2_2") (pintype "passive"))
    )
    (net (code "34") (name "Net-(IC3-GBUF)") (class "Default")
      (node (ref "IC3") (pin "42") (pinfunction "GBUF_42") (pintype "passive"))
      (node (ref "R5") (pin "2") (pinfunction "2_2") (pintype "passive"))
      (node (ref "X3") (pin "1") (pinfunction "1_1") (pintype "passive"))
    )
    (net (code "35") (name "Net-(IC3-GPIO0)") (class "Default")
      (node (ref "IC3") (pin "33") (pinfunction "GPIO0_33") (pintype "bidirectional"))
      (node (ref "IC3") (pin "34") (pinfunction "GPIO1_34") (pintype "bidirectional"))
      (node (ref "IC3") (pin "36") (pinfunction "GPIO4_36") (pintype "bidirectional"))
      (node (ref "R15") (pin "2") (pinfunction "2_2") (pintype "passive"))
    )
    (net (code "36") (name "Net-(IC3-GPIO2)") (class "Default")
      (node (ref "IC3") (pin "10") (pinfunction "GPIO3_10") (pintype "bidirectional"))
      (node (ref "IC3") (pin "11") (pinfunction "GPIO6_11") (pintype "bidirectional"))
      (node (ref "IC3") (pin "12") (pinfunction "GPIO7_12") (pintype "bidirectional"))
      (node (ref "IC3") (pin "9") (pinfunction "GPIO2_9") (pintype "bidirectional"))
      (node (ref "R8") (pin "2") (pinfunction "2_2") (pintype "passive"))
    )
    (net (code "37") (name "Net-(IC3-GPIO5)") (class "Default")
      (node (ref "IC3") (pin "25") (pinfunction "GPIO5_25") (pintype "bidirectional"))
      (node (ref "R17") (pin "2") (pinfunction "2_2") (pintype "passive"))
    )
    (net (code "38") (name "Net-(IC3-LEFT)") (class "Default")
      (node (ref "IC3") (pin "46") (pinfunction "LEFT_46") (pintype "passive"))
      (node (ref "R3") (pin "2") (pinfunction "2_2") (pintype "passive"))
      (node (ref "X3") (pin "3") (pinfunction "3_3") (pintype "passive"))
    )
    (net (code "39") (name "Net-(IC3-RCAP)") (class "Default")
      (node (ref "C13") (pin "1") (pinfunction "1_1") (pintype "passive"))
      (node (ref "IC3") (pin "44") (pinfunction "RCAP_44") (pintype "passive"))
    )
    (net (code "40") (name "Net-(IC3-RIGHT)") (class "Default")
      (node (ref "IC3") (pin "39") (pinfunction "RIGHT_39") (pintype "passive"))
      (node (ref "R4") (pin "2") (pinfunction "2_2") (pintype "passive"))
      (node (ref "X3") (pin "2") (pinfunction "2_2") (pintype "passive"))
    )
    (net (code "41") (name "Net-(IC3-XTALI)") (class "Default")
      (node (ref "C12") (pin "1") (pinfunction "1_1") (pintype "passive"))
      (node (ref "IC3") (pin "18") (pinfunction "XTALI_18") (pintype "passive"))
      (node (ref "Q1") (pin "1") (pinfunction "1_1") (pintype "passive"))
      (node (ref "R2") (pin "1") (pinfunction "1_1") (pintype "passive"))
    )
    (net (code "42") (name "Net-(IC3-XTALO)") (class "Default")
      (node (ref "C11") (pin "1") (pinfunction "1_1") (pintype "passive"))
      (node (ref "IC3") (pin "17") (pinfunction "XTALO_17") (pintype "passive"))
      (node (ref "Q1") (pin "2") (pinfunction "2_2") (pintype "passive"))
      (node (ref "R2") (pin "2") (pinfunction "2_2") (pintype "passive"))
    )
    (net (code "43") (name "Net-(IC3-~{RESET})") (class "Default")
      (node (ref "IC3") (pin "3") (pinfunction "~{RESET}_3") (pintype "input"))
      (node (ref "R7") (pin "2") (pinfunction "2_2") (pintype "passive"))
    )
    (net (code "44") (name "Net-(JP1-Pad4)") (class "Default")
      (node (ref "JP1") (pin "4") (pinfunction "4_4") (pintype "passive"))
      (node (ref "R1") (pin "3") (pinfunction "3_3") (pintype "passive"))
    )
    (net (code "45") (name "Net-(JP1-Pad10)") (class "Default")
      (node (ref "JP1") (pin "10") (pinfunction "10_10") (pintype "passive"))
      (node (ref "R16") (pin "2") (pinfunction "2_2") (pintype "passive"))
    )
    (net (code "46") (name "Net-(R9-Pad1)") (class "Default")
      (node (ref "R9") (pin "1") (pinfunction "1_1") (pintype "passive"))
      (node (ref "X1") (pin "1") (pinfunction "1_1") (pintype "passive"))
    )
    (net (code "47") (name "Net-(U1-ADJ)") (class "Default")
      (node (ref "R20") (pin "1") (pinfunction "1_1") (pintype "passive"))
      (node (ref "R21") (pin "1") (pinfunction "1_1") (pintype "passive"))
      (node (ref "U1") (pin "1") (pinfunction "ADJ_1") (pintype "passive"))
    )
    (net (code "48") (name "Net-(U2-ADJ)") (class "Default")
      (node (ref "R18") (pin "1") (pinfunction "1_1") (pintype "passive"))
      (node (ref "R19") (pin "1") (pinfunction "1_1") (pintype "passive"))
      (node (ref "U2") (pin "1") (pinfunction "ADJ_1") (pintype "passive"))
    )
    (net (code "49") (name "Net-(X4-N)") (class "Default")
      (node (ref "X4") (pin "1") (pinfunction "N_1") (pintype "input"))
      (node (ref "X5") (pin "1") (pinfunction "KL_1") (pintype "passive"))
    )
    (net (code "50") (name "SCK") (class "Default")
      (node (ref "IC1") (pin "8") (pinfunction "(SCK/PCINT15)PB7_8") (pintype "bidirectional"))
      (node (ref "IC4") (pin "5") (pinfunction "I_5") (pintype "input"))
      (node (ref "JP3") (pin "3") (pinfunction "3_3") (pintype "passive"))
    )
    (net (code "51") (name "SCK_3V") (class "Default")
      (node (ref "IC3") (pin "28") (pinfunction "SCLK_28") (pintype "input"))
      (node (ref "IC4") (pin "4") (pinfunction "O_4") (pintype "output"))
      (node (ref "X2") (pin "5") (pinfunction "5_5") (pintype "bidirectional"))
    )
    (net (code "52") (name "SD_~{CS}") (class "Default")
      (node (ref "IC4") (pin "6") (pinfunction "O_6") (pintype "output"))
      (node (ref "X2") (pin "2") (pinfunction "2_2") (pintype "bidirectional"))
    )
    (net (code "53") (name "SD_~{CS}_I") (class "Default")
      (node (ref "IC1") (pin "5") (pinfunction "(OC0B/~{SS}/PCINT12)PB4_5") (pintype "bidirectional"))
      (node (ref "IC4") (pin "7") (pinfunction "I_7") (pintype "input"))
      (node (ref "R14") (pin "2") (pinfunction "2_2") (pintype "passive"))
    )
    (net (code "54") (name "SW_0") (class "Default")
      (node (ref "IC1") (pin "40") (pinfunction "(ADC0/PCINT0)PA0_40") (pintype "bidirectional"))
      (node (ref "SV1") (pin "1") (pinfunction "1_1") (pintype "passive"))
    )
    (net (code "55") (name "SW_1") (class "Default")
      (node (ref "IC1") (pin "39") (pinfunction "(ADC1/PCINT1)PA1_39") (pintype "bidirectional"))
      (node (ref "SV1") (pin "2") (pinfunction "2_2") (pintype "passive"))
    )
    (net (code "56") (name "SW_2") (class "Default")
      (node (ref "IC1") (pin "38") (pinfunction "(ADC2/PCINT2)PA2_38") (pintype "bidirectional"))
      (node (ref "SV1") (pin "3") (pinfunction "3_3") (pintype "passive"))
    )
    (net (code "57") (name "SW_3") (class "Default")
      (node (ref "IC1") (pin "37") (pinfunction "(ADC3/PCINT3)PA3_37") (pintype "bidirectional"))
      (node (ref "SV1") (pin "4") (pinfunction "4_4") (pintype "passive"))
    )
    (net (code "58") (name "SW_4") (class "Default")
      (node (ref "IC1") (pin "36") (pinfunction "(ADC4/PCINT4)PA4_36") (pintype "bidirectional"))
      (node (ref "SV1") (pin "5") (pinfunction "5_5") (pintype "passive"))
    )
    (net (code "59") (name "SW_5") (class "Default")
      (node (ref "IC1") (pin "35") (pinfunction "(ADC5/PCINT5)PA5_35") (pintype "bidirectional"))
      (node (ref "SV1") (pin "6") (pinfunction "6_6") (pintype "passive"))
    )
    (net (code "60") (name "SW_6") (class "Default")
      (node (ref "IC1") (pin "34") (pinfunction "(ADC6/PCINT6)PA6_34") (pintype "bidirectional"))
      (node (ref "SV1") (pin "7") (pinfunction "7_7") (pintype "passive"))
    )
    (net (code "61") (name "SW_7") (class "Default")
      (node (ref "IC1") (pin "33") (pinfunction "(ADC7/PCINT7)PA7_33") (pintype "bidirectional"))
      (node (ref "SV1") (pin "8") (pinfunction "8_8") (pintype "passive"))
    )
    (net (code "62") (name "SW_A") (class "Default")
      (node (ref "SV2") (pin "7") (pinfunction "7_7") (pintype "passive"))
      (node (ref "SW2") (pin "B@1") (pinfunction "B_B@1") (pintype "passive"))
      (node (ref "SW2") (pin "B@2") (pinfunction "B_B@2") (pintype "passive"))
    )
    (net (code "63") (name "SW_B") (class "Default")
      (node (ref "SV2") (pin "1") (pinfunction "1_1") (pintype "passive"))
      (node (ref "SW3") (pin "B@1") (pinfunction "B_B@1") (pintype "passive"))
      (node (ref "SW3") (pin "B@2") (pinfunction "B_B@2") (pintype "passive"))
    )
    (net (code "64") (name "SW_C") (class "Default")
      (node (ref "SV2") (pin "2") (pinfunction "2_2") (pintype "passive"))
      (node (ref "SW4") (pin "B@1") (pinfunction "B_B@1") (pintype "passive"))
      (node (ref "SW4") (pin "B@2") (pinfunction "B_B@2") (pintype "passive"))
    )
    (net (code "65") (name "SW_D") (class "Default")
      (node (ref "SV2") (pin "8") (pinfunction "8_8") (pintype "passive"))
      (node (ref "SW5") (pin "B@1") (pinfunction "B_B@1") (pintype "passive"))
      (node (ref "SW5") (pin "B@2") (pinfunction "B_B@2") (pintype "passive"))
    )
    (net (code "66") (name "SW_E") (class "Default")
      (node (ref "SV2") (pin "3") (pinfunction "3_3") (pintype "passive"))
      (node (ref "SW6") (pin "B@1") (pinfunction "B_B@1") (pintype "passive"))
      (node (ref "SW6") (pin "B@2") (pinfunction "B_B@2") (pintype "passive"))
    )
    (net (code "67") (name "SW_F") (class "Default")
      (node (ref "SV2") (pin "5") (pinfunction "5_5") (pintype "passive"))
      (node (ref "SW1") (pin "A") (pinfunction "A_A") (pintype "passive"))
    )
    (net (code "68") (name "SW_G") (class "Default")
      (node (ref "SV2") (pin "4") (pinfunction "4_4") (pintype "passive"))
      (node (ref "SW1") (pin "B") (pinfunction "B_B") (pintype "passive"))
    )
    (net (code "69") (name "SW_H") (class "Default")
      (node (ref "SV2") (pin "6") (pinfunction "6_6") (pintype "passive"))
      (node (ref "SW1") (pin "P1") (pinfunction "1_P1") (pintype "passive"))
    )
    (net (code "70") (name "VS_RXD") (class "Default")
      (node (ref "IC3") (pin "26") (pinfunction "RX_26") (pintype "input"))
      (node (ref "JP2") (pin "1") (pinfunction "1_1") (pintype "passive"))
      (node (ref "R6") (pin "1") (pinfunction "1_1") (pintype "passive"))
    )
    (net (code "71") (name "VS_TXD") (class "Default")
      (node (ref "IC3") (pin "27") (pinfunction "TX_27") (pintype "output"))
      (node (ref "JP2") (pin "2") (pinfunction "2_2") (pintype "passive"))
    )
    (net (code "72") (name "VS_~{CS}") (class "Default")
      (node (ref "IC3") (pin "23") (pinfunction "~{CS}_23") (pintype "input"))
      (node (ref "IC4") (pin "10") (pinfunction "O_10") (pintype "output"))
    )
    (net (code "73") (name "VS_~{CS}_I") (class "Default")
      (node (ref "IC1") (pin "4") (pinfunction "(OC0A/AIN1/PCINT11)PB3_4") (pintype "bidirectional"))
      (node (ref "IC4") (pin "9") (pinfunction "I_9") (pintype "input"))
      (node (ref "R13") (pin "2") (pinfunction "2_2") (pintype "passive"))
    )
    (net (code "74") (name "VS_~{DCS}") (class "Default")
      (node (ref "IC3") (pin "13") (pinfunction "~{DCS}_13") (pintype "input"))
      (node (ref "IC4") (pin "12") (pinfunction "O_12") (pintype "output"))
    )
    (net (code "75") (name "VS_~{DREQ}") (class "Default")
      (node (ref "IC1") (pin "2") (pinfunction "(CLKO/T1/PCINT9)PB1_2") (pintype "bidirectional"))
      (node (ref "IC3") (pin "8") (pinfunction "~{DREQ}_8") (pintype "input"))
    )
    (net (code "76") (name "unconnected-(IC1-(OC2A{slash}PCINT31)PD7-Pad21)") (class "Default")
      (node (ref "IC1") (pin "21") (pinfunction "(OC2A/PCINT31)PD7_21") (pintype "bidirectional"))
    )
    (net (code "77") (name "unconnected-(IC1-(OC2B{slash}ICP{slash}PCINT30)PD6-Pad20)") (class "Default")
      (node (ref "IC1") (pin "20") (pinfunction "(OC2B/ICP/PCINT30)PD6_20") (pintype "bidirectional"))
    )
    (net (code "78") (name "unconnected-(IC2-CBUS0-Pad23)") (class "Default")
      (node (ref "IC2") (pin "23") (pinfunction "CBUS0_23") (pintype "bidirectional"))
    )
    (net (code "79") (name "unconnected-(IC2-CBUS1-Pad22)") (class "Default")
      (node (ref "IC2") (pin "22") (pinfunction "CBUS1_22") (pintype "bidirectional"))
    )
    (net (code "80") (name "unconnected-(IC2-CBUS2-Pad13)") (class "Default")
      (node (ref "IC2") (pin "13") (pinfunction "CBUS2_13") (pintype "bidirectional"))
    )
    (net (code "81") (name "unconnected-(IC2-CBUS3-Pad14)") (class "Default")
      (node (ref "IC2") (pin "14") (pinfunction "CBUS3_14") (pintype "bidirectional"))
    )
    (net (code "82") (name "unconnected-(IC2-CBUS4-Pad12)") (class "Default")
      (node (ref "IC2") (pin "12") (pinfunction "CBUS4_12") (pintype "bidirectional"))
    )
    (net (code "83") (name "unconnected-(IC2-OSCI-Pad27)") (class "Default")
      (node (ref "IC2") (pin "27") (pinfunction "OSCI_27") (pintype "input"))
    )
    (net (code "84") (name "unconnected-(IC2-OSCO-Pad28)") (class "Default")
      (node (ref "IC2") (pin "28") (pinfunction "OSCO_28") (pintype "output"))
    )
    (net (code "85") (name "unconnected-(IC2-~{CTS}-Pad11)") (class "Default")
      (node (ref "IC2") (pin "11") (pinfunction "~{CTS}_11") (pintype "input"))
    )
    (net (code "86") (name "unconnected-(IC2-~{DCD}-Pad10)") (class "Default")
      (node (ref "IC2") (pin "10") (pinfunction "~{DCD}_10") (pintype "input"))
    )
    (net (code "87") (name "unconnected-(IC2-~{DSR}-Pad9)") (class "Default")
      (node (ref "IC2") (pin "9") (pinfunction "~{DSR}_9") (pintype "input"))
    )
    (net (code "88") (name "unconnected-(IC2-~{DTR}-Pad2)") (class "Default")
      (node (ref "IC2") (pin "2") (pinfunction "~{DTR}_2") (pintype "output"))
    )
    (net (code "89") (name "unconnected-(IC2-~{RI}-Pad6)") (class "Default")
      (node (ref "IC2") (pin "6") (pinfunction "~{RI}_6") (pintype "input"))
    )
    (net (code "90") (name "unconnected-(IC2-~{RTS}-Pad3)") (class "Default")
      (node (ref "IC2") (pin "3") (pinfunction "~{RTS}_3") (pintype "output"))
    )
    (net (code "91") (name "unconnected-(IC3-LINE2-Pad48)") (class "Default")
      (node (ref "IC3") (pin "48") (pinfunction "LINE2_48") (pintype "passive"))
    )
    (net (code "92") (name "unconnected-(IC3-MIC+{slash}LINE1-Pad1)") (class "Default")
      (node (ref "IC3") (pin "1") (pinfunction "MIC+/LINE1_1") (pintype "passive"))
    )
    (net (code "93") (name "unconnected-(IC3-MIC--Pad2)") (class "Default")
      (node (ref "IC3") (pin "2") (pinfunction "MIC-_2") (pintype "passive"))
    )
    (net (code "94") (name "unconnected-(IC3-VCO-Pad15)") (class "Default")
      (node (ref "IC3") (pin "15") (pinfunction "VCO_15") (pintype "output"))
    )
    (net (code "95") (name "unconnected-(IC4F-I-Pad14)") (class "Default")
      (node (ref "IC4") (pin "14") (pinfunction "I_14") (pintype "input"))
    )
    (net (code "96") (name "unconnected-(IC4F-O-Pad15)") (class "Default")
      (node (ref "IC4") (pin "15") (pinfunction "O_15") (pintype "output"))
    )
    (net (code "97") (name "unconnected-(JP1-Pad20)") (class "Default")
      (node (ref "JP1") (pin "20") (pinfunction "20_20") (pintype "passive"))
    )
    (net (code "98") (name "unconnected-(X1-Pad5)") (class "Default")
      (node (ref "X1") (pin "5") (pinfunction "5_5") (pintype "passive"))
    )
    (net (code "99") (name "unconnected-(X2-Pad1)") (class "Default")
      (node (ref "X2") (pin "1") (pinfunction "1_1") (pintype "bidirectional"))
    )
    (net (code "100") (name "unconnected-(X2-Pad8)") (class "Default")
      (node (ref "X2") (pin "8") (pinfunction "8_8") (pintype "bidirectional"))
    )
    (net (code "101") (name "unconnected-(X3-Pad4)") (class "Default")
      (node (ref "X3") (pin "4") (pinfunction "4_4") (pintype "passive"))
    )
    (net (code "102") (name "unconnected-(X3-Pad5)") (class "Default")
      (node (ref "X3") (pin "5") (pinfunction "5_5") (pintype "passive"))
    )
    (net (code "103") (name "~{CE}") (class "Default")
      (node (ref "IC1") (pin "17") (pinfunction "(TXD1/INT1/PCINT27)PD3_17") (pintype "bidirectional"))
      (node (ref "JP1") (pin "8") (pinfunction "8_8") (pintype "passive"))
    )
    (net (code "104") (name "~{RD}") (class "Default")
      (node (ref "IC1") (pin "18") (pinfunction "(XCK1/OC1B/PCINT28)PD4_18") (pintype "bidirectional"))
      (node (ref "JP1") (pin "7") (pinfunction "7_7") (pintype "passive"))
    )
    (net (code "105") (name "~{RESET}") (class "Default")
      (node (ref "C26") (pin "1") (pinfunction "1_1") (pintype "passive"))
      (node (ref "IC1") (pin "9") (pinfunction "~{RESET}_9") (pintype "input"))
      (node (ref "JP1") (pin "11") (pinfunction "11_11") (pintype "passive"))
      (node (ref "JP3") (pin "5") (pinfunction "5_5") (pintype "passive"))
      (node (ref "R11") (pin "1") (pinfunction "1_1") (pintype "passive"))
    )
    (net (code "106") (name "~{WR}") (class "Default")
      (node (ref "IC1") (pin "16") (pinfunction "(RXD1/INT0/PCINT26)PD2_16") (pintype "bidirectional"))
      (node (ref "JP1") (pin "6") (pinfunction "6_6") (pintype "passive"))
    )
  )
)
